# mk6.net
KiCad netlist of a schematic drawn in EAGLE
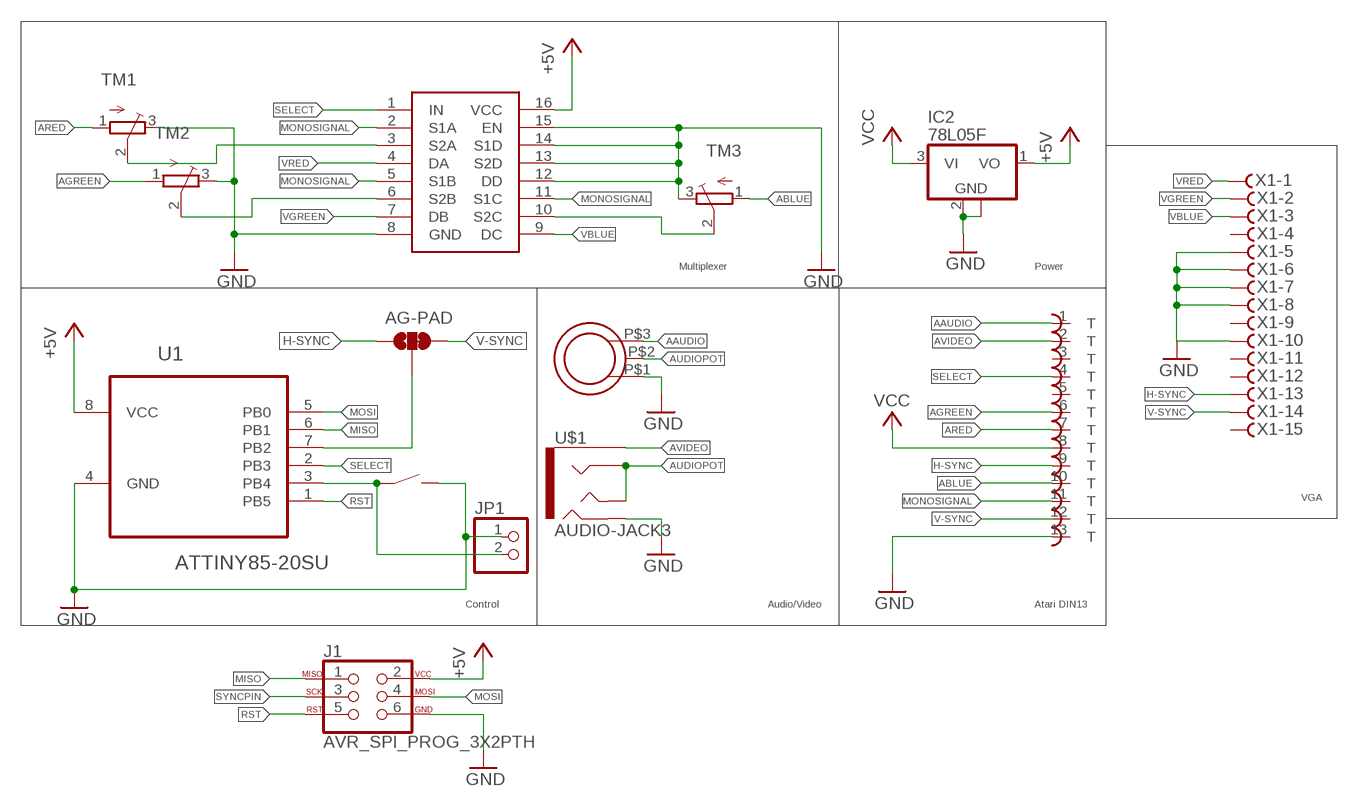
[diagram p0: schematic, sheet 1]

(export (version "E")
  (design (tool "Eeschema 10.0.6"))
  (components
    (comp (ref "AG-PAD")
      (value "JUMPER-SMT_3_1-NC_TRACE_SILK")
      (footprint "eagle-import:SMT-JUMPER_3_1-NC_TRACE_SILK")
      (libsource (lib "eagle-import") (part "JUMPER-SMT_3_1-NC_TRACE_SILK"))
    )
    (comp (ref "ATARIOUT")
      (value "DIN13T")
      (footprint "eagle-import:ADADS")
      (libsource (lib "eagle-import") (part "DIN13T"))
    )
    (comp (ref "IC2")
      (value "78L05F")
      (footprint "eagle-import:SOT89")
      (libsource (lib "eagle-import") (part "78LF05"))
    )
    (comp (ref "J1")
      (value "AVR_SPI_PROG_3X2PTH")
      (footprint "eagle-import:2X3")
      (libsource (lib "eagle-import") (part "AVR_SPI_PROG_3X2PTH"))
    )
    (comp (ref "JP1")
      (value "PINHD-1X2")
      (footprint "eagle-import:1X02")
      (libsource (lib "eagle-import") (part "PINHD-1X2"))
    )
    (comp (ref "S2")
      (value "K2-1823SA")
      (footprint "eagle-import:K2-1823SA")
      (libsource (lib "eagle-import") (part "K2-1823SA"))
    )
    (comp (ref "TM1")
      (value "TRIMPOTTC33X")
      (footprint "eagle-import:TC33X")
      (libsource (lib "eagle-import") (part "TRIMPOTTC33X"))
    )
    (comp (ref "TM2")
      (value "TRIMPOTTC33X")
      (footprint "eagle-import:TC33X")
      (libsource (lib "eagle-import") (part "TRIMPOTTC33X"))
    )
    (comp (ref "TM3")
      (value "TRIMPOTTC33X")
      (footprint "eagle-import:TC33X")
      (libsource (lib "eagle-import") (part "TRIMPOTTC33X"))
    )
    (comp (ref "TS5V330")
      (value "V330")
      (footprint "eagle-import:SOIC16N")
      (libsource (lib "eagle-import") (part "V330"))
    )
    (comp (ref "U$1")
      (value "AUDIO-JACK3")
      (footprint "eagle-import:AUDIO-JACK-TRRS-SMD")
      (libsource (lib "eagle-import") (part "AUDIO-JACK3"))
    )
    (comp (ref "U$2")
      (value "DB-1001N")
      (footprint "eagle-import:THUMB_POT")
      (libsource (lib "eagle-import") (part "DB-1001N"))
    )
    (comp (ref "U1")
      (value "ATTINY85-20SU")
      (footprint "eagle-import:SOIC127P798X216-8N")
      (libsource (lib "eagle-import") (part "ATTINY85-20SU"))
    )
    (comp (ref "X1")
      (value "F15HDVS")
      (footprint "eagle-import:HDF15V")
      (libsource (lib "eagle-import") (part "F15?SHDV"))
    )
  )
  (nets
    (net (code "1") (name "+5V") (class "Default")
      (node (ref "IC2") (pin "1") (pinfunction "VO_1") (pintype "passive"))
      (node (ref "J1") (pin "2") (pinfunction "2_2") (pintype "passive"))
      (node (ref "TS5V330") (pin "16") (pinfunction "VCC_16") (pintype "bidirectional"))
      (node (ref "U1") (pin "8") (pinfunction "VCC_8") (pintype "power_in"))
    )
    (net (code "2") (name "AAUDIO") (class "Default")
      (node (ref "ATARIOUT") (pin "1") (pinfunction "T_1") (pintype "passive"))
      (node (ref "U$2") (pin "P$3") (pinfunction "3_P$3") (pintype "bidirectional"))
    )
    (net (code "3") (name "ABLUE") (class "Default")
      (node (ref "ATARIOUT") (pin "10") (pinfunction "T_10") (pintype "passive"))
      (node (ref "TM3") (pin "1") (pinfunction "A_1") (pintype "passive"))
    )
    (net (code "4") (name "AGREEN") (class "Default")
      (node (ref "ATARIOUT") (pin "6") (pinfunction "T_6") (pintype "passive"))
      (node (ref "TM2") (pin "1") (pinfunction "A_1") (pintype "passive"))
    )
    (net (code "5") (name "ARED") (class "Default")
      (node (ref "ATARIOUT") (pin "7") (pinfunction "T_7") (pintype "passive"))
      (node (ref "TM1") (pin "1") (pinfunction "A_1") (pintype "passive"))
    )
    (net (code "6") (name "AUDIOPOT") (class "Default")
      (node (ref "U$1") (pin "RING1") (pinfunction "RING1_RING1") (pintype "bidirectional"))
      (node (ref "U$1") (pin "TIP") (pinfunction "TIP_TIP") (pintype "bidirectional"))
      (node (ref "U$2") (pin "P$2") (pinfunction "2_P$2") (pintype "bidirectional"))
    )
    (net (code "7") (name "AVIDEO") (class "Default")
      (node (ref "ATARIOUT") (pin "2") (pinfunction "T_2") (pintype "passive"))
      (node (ref "U$1") (pin "EARTH") (pinfunction "EARTH_EARTH") (pintype "bidirectional"))
    )
    (net (code "8") (name "GND") (class "Default")
      (node (ref "ATARIOUT") (pin "13") (pinfunction "T_13") (pintype "passive"))
      (node (ref "IC2") (pin "2") (pinfunction "GND_2") (pintype "passive"))
      (node (ref "IC2") (pin "2@1") (pinfunction "GND_2@1") (pintype "passive"))
      (node (ref "J1") (pin "6") (pinfunction "6_6") (pintype "passive"))
      (node (ref "JP1") (pin "1") (pinfunction "1_1") (pintype "passive"))
      (node (ref "S2") (pin "P$2") (pinfunction "2_P$2") (pintype "bidirectional"))
      (node (ref "TM1") (pin "3") (pinfunction "E_3") (pintype "passive"))
      (node (ref "TM2") (pin "3") (pinfunction "E_3") (pintype "passive"))
      (node (ref "TM3") (pin "3") (pinfunction "E_3") (pintype "passive"))
      (node (ref "TS5V330") (pin "12") (pinfunction "DD_12") (pintype "bidirectional"))
      (node (ref "TS5V330") (pin "13") (pinfunction "S2D_13") (pintype "bidirectional"))
      (node (ref "TS5V330") (pin "14") (pinfunction "S1D_14") (pintype "bidirectional"))
      (node (ref "TS5V330") (pin "15") (pinfunction "EN_15") (pintype "bidirectional"))
      (node (ref "TS5V330") (pin "8") (pinfunction "GND_8") (pintype "bidirectional"))
      (node (ref "U$1") (pin "RING2") (pinfunction "RING2_RING2") (pintype "bidirectional"))
      (node (ref "U$2") (pin "P$1") (pinfunction "1_P$1") (pintype "bidirectional"))
      (node (ref "U1") (pin "4") (pinfunction "GND_4") (pintype "passive"))
      (node (ref "X1") (pin "10") (pinfunction "F_10") (pintype "passive"))
      (node (ref "X1") (pin "5") (pinfunction "F_5") (pintype "passive"))
      (node (ref "X1") (pin "6") (pinfunction "F_6") (pintype "passive"))
      (node (ref "X1") (pin "7") (pinfunction "F_7") (pintype "passive"))
      (node (ref "X1") (pin "8") (pinfunction "F_8") (pintype "passive"))
    )
    (net (code "9") (name "H-SYNC") (class "Default")
      (node (ref "AG-PAD") (pin "1") (pinfunction "1_1") (pintype "passive"))
      (node (ref "ATARIOUT") (pin "9") (pinfunction "T_9") (pintype "passive"))
      (node (ref "X1") (pin "13") (pinfunction "F_13") (pintype "passive"))
    )
    (net (code "10") (name "MISO") (class "Default")
      (node (ref "J1") (pin "1") (pinfunction "1_1") (pintype "passive"))
      (node (ref "U1") (pin "6") (pinfunction "PB1_6") (pintype "bidirectional"))
    )
    (net (code "11") (name "MONOSIGNAL") (class "Default")
      (node (ref "ATARIOUT") (pin "11") (pinfunction "T_11") (pintype "passive"))
      (node (ref "TS5V330") (pin "11") (pinfunction "S1C_11") (pintype "bidirectional"))
      (node (ref "TS5V330") (pin "2") (pinfunction "S1A_2") (pintype "bidirectional"))
      (node (ref "TS5V330") (pin "5") (pinfunction "S1B_5") (pintype "bidirectional"))
    )
    (net (code "12") (name "MOSI") (class "Default")
      (node (ref "J1") (pin "4") (pinfunction "4_4") (pintype "passive"))
      (node (ref "U1") (pin "5") (pinfunction "PB0_5") (pintype "bidirectional"))
    )
    (net (code "13") (name "Net-(S2-1)") (class "Default")
      (node (ref "JP1") (pin "2") (pinfunction "2_2") (pintype "passive"))
      (node (ref "S2") (pin "P$1") (pinfunction "1_P$1") (pintype "bidirectional"))
      (node (ref "U1") (pin "3") (pinfunction "PB4_3") (pintype "bidirectional"))
    )
    (net (code "14") (name "Net-(TM1-S)") (class "Default")
      (node (ref "TM1") (pin "2") (pinfunction "S_2") (pintype "passive"))
      (node (ref "TS5V330") (pin "3") (pinfunction "S2A_3") (pintype "bidirectional"))
    )
    (net (code "15") (name "Net-(TM2-S)") (class "Default")
      (node (ref "TM2") (pin "2") (pinfunction "S_2") (pintype "passive"))
      (node (ref "TS5V330") (pin "6") (pinfunction "S2B_6") (pintype "bidirectional"))
    )
    (net (code "16") (name "Net-(TM3-S)") (class "Default")
      (node (ref "TM3") (pin "2") (pinfunction "S_2") (pintype "passive"))
      (node (ref "TS5V330") (pin "10") (pinfunction "S2C_10") (pintype "bidirectional"))
    )
    (net (code "17") (name "RST") (class "Default")
      (node (ref "J1") (pin "5") (pinfunction "5_5") (pintype "passive"))
      (node (ref "U1") (pin "1") (pinfunction "PB5_1") (pintype "bidirectional"))
    )
    (net (code "18") (name "SELECT") (class "Default")
      (node (ref "ATARIOUT") (pin "4") (pinfunction "T_4") (pintype "passive"))
      (node (ref "TS5V330") (pin "1") (pinfunction "IN_1") (pintype "bidirectional"))
      (node (ref "U1") (pin "2") (pinfunction "PB3_2") (pintype "bidirectional"))
    )
    (net (code "19") (name "SYNCPIN") (class "Default")
      (node (ref "AG-PAD") (pin "2") (pinfunction "2_2") (pintype "passive"))
      (node (ref "J1") (pin "3") (pinfunction "3_3") (pintype "passive"))
      (node (ref "U1") (pin "7") (pinfunction "PB2_7") (pintype "bidirectional"))
    )
    (net (code "20") (name "V-SYNC") (class "Default")
      (node (ref "AG-PAD") (pin "3") (pinfunction "3_3") (pintype "passive"))
      (node (ref "ATARIOUT") (pin "12") (pinfunction "T_12") (pintype "passive"))
      (node (ref "X1") (pin "14") (pinfunction "F_14") (pintype "passive"))
    )
    (net (code "21") (name "VBLUE") (class "Default")
      (node (ref "TS5V330") (pin "9") (pinfunction "DC_9") (pintype "bidirectional"))
      (node (ref "X1") (pin "3") (pinfunction "F_3") (pintype "passive"))
    )
    (net (code "22") (name "VCC") (class "Default")
      (node (ref "ATARIOUT") (pin "8") (pinfunction "T_8") (pintype "passive"))
      (node (ref "IC2") (pin "3") (pinfunction "VI_3") (pintype "input"))
    )
    (net (code "23") (name "VGREEN") (class "Default")
      (node (ref "TS5V330") (pin "7") (pinfunction "DB_7") (pintype "bidirectional"))
      (node (ref "X1") (pin "2") (pinfunction "F_2") (pintype "passive"))
    )
    (net (code "24") (name "VRED") (class "Default")
      (node (ref "TS5V330") (pin "4") (pinfunction "DA_4") (pintype "bidirectional"))
      (node (ref "X1") (pin "1") (pinfunction "F_1") (pintype "passive"))
    )
    (net (code "25") (name "unconnected-(ATARIOUTG-T-Pad3)") (class "Default")
      (node (ref "ATARIOUT") (pin "3") (pinfunction "T_3") (pintype "passive"))
    )
    (net (code "26") (name "unconnected-(ATARIOUTI-T-Pad5)") (class "Default")
      (node (ref "ATARIOUT") (pin "5") (pinfunction "T_5") (pintype "passive"))
    )
    (net (code "27") (name "unconnected-(X1C-F-Pad11)") (class "Default")
      (node (ref "X1") (pin "11") (pinfunction "F_11") (pintype "passive"))
    )
    (net (code "28") (name "unconnected-(X1D-F-Pad12)") (class "Default")
      (node (ref "X1") (pin "12") (pinfunction "F_12") (pintype "passive"))
    )
    (net (code "29") (name "unconnected-(X1G-F-Pad15)") (class "Default")
      (node (ref "X1") (pin "15") (pinfunction "F_15") (pintype "passive"))
    )
    (net (code "30") (name "unconnected-(X1J-F-Pad4)") (class "Default")
      (node (ref "X1") (pin "4") (pinfunction "F_4") (pintype "passive"))
    )
    (net (code "31") (name "unconnected-(X1O-F-Pad9)") (class "Default")
      (node (ref "X1") (pin "9") (pinfunction "F_9") (pintype "passive"))
    )
  )
)
